# 12VDC_3V3DC_LM2596.net
KiCad netlist of a schematic drawn in Altium Designer
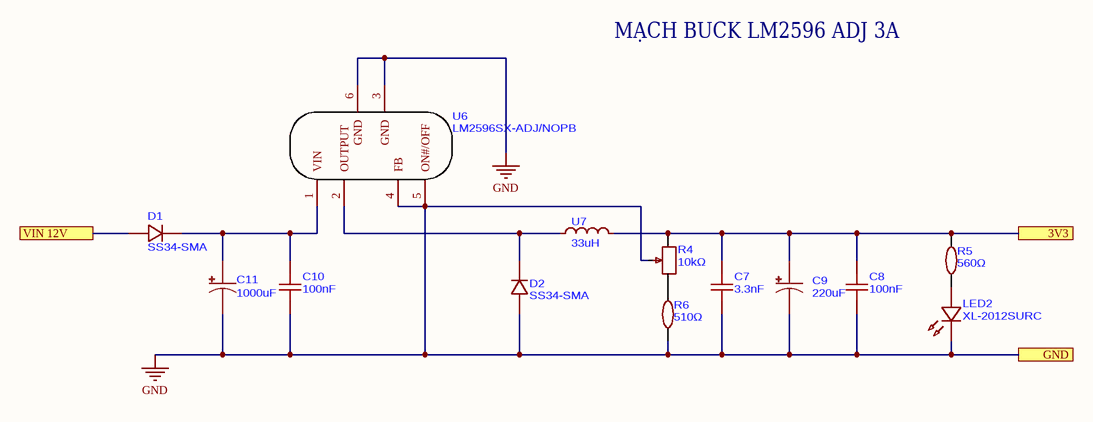
[diagram p0: 12VDC_3V3DC_LM2596.SchDoc]

(export (version "E")
  (design (tool "Eeschema 10.0.6"))
  (components
    (comp (ref "C7")
      (value "3.3nF")
      (footprint "C0805")
      (libsource (lib "CAP 0.1uF") (part "CC0805KRX7R9BB104"))
    )
    (comp (ref "C8")
      (value "100nF")
      (footprint "C0805")
      (libsource (lib "CAP 0.1uF") (part "CC0805KRX7R9BB104"))
    )
    (comp (ref "C9")
      (value "220uF")
      (footprint "CAP-SMD_BD10.0-L10.3-W10.3-LS11.0-R-RD")
      (libsource (lib "CAP +") (part "VEJ102M1ATR-1010"))
    )
    (comp (ref "C10")
      (value "100nF")
      (footprint "C0805")
      (libsource (lib "CAP 0.1uF") (part "CC0805KRX7R9BB104"))
    )
    (comp (ref "C11")
      (value "1000uF")
      (footprint "CAP-SMD_BD10.0-L10.3-W10.3-LS11.0-R-RD")
      (libsource (lib "CAP +") (part "VEJ102M1ATR-1010"))
    )
    (comp (ref "D1")
      (value "SS34-SMA")
      (footprint "SMA_L4.3-W2.6-LS5.2-RD")
      (libsource (lib "Diode SS34") (part "SS34-SMA"))
    )
    (comp (ref "D2")
      (value "SS34-SMA")
      (footprint "SMA_L4.3-W2.6-LS5.2-RD")
      (libsource (lib "Diode SS34") (part "SS34-SMA"))
    )
    (comp (ref "LED2")
      (value "XL-2012SURC")
      (footprint "LED0805-RD_RED")
      (libsource (lib "LED_RED") (part "XL-2012SURC"))
    )
    (comp (ref "R4")
      (value "10kΩ")
      (footprint "RES-ADJ-TH_3296W")
      (libsource (lib "VR 10K") (part "3296W-1-103_C330432"))
    )
    (comp (ref "R5") (value "560Ω") (footprint "R0805") (libsource (lib "RES 1K") (part "RC0805FR-071KL")))
    (comp (ref "R6") (value "510Ω") (footprint "R0805") (libsource (lib "RES 1K") (part "RC0805FR-071KL")))
    (comp (ref "U6")
      (value "LM2596SX-ADJ/NOPB")
      (footprint "TO-263-5_L10.2-W8.9-P1.70-TL")
      (libsource (lib "LM2596") (part "LM2596SX-ADJ/NOPB"))
    )
    (comp (ref "U7")
      (value "33uH")
      (footprint "IND-SMD_L10.0-W10.0_744066100")
      (libsource (lib "Inductor") (part "SRU1038-330Y"))
    )
  )
  (nets
    (net (code "1") (name "/3V3") (class "Default")
      (node (ref "C7") (pin "2") (pinfunction "2_2") (pintype "passive"))
      (node (ref "C8") (pin "2") (pinfunction "2_2") (pintype "passive"))
      (node (ref "C9") (pin "1") (pinfunction "1_1") (pintype "passive"))
      (node (ref "R4") (pin "1") (pinfunction "1_1") (pintype "passive"))
      (node (ref "R5") (pin "2") (pinfunction "2_2") (pintype "passive"))
      (node (ref "U7") (pin "2") (pinfunction "2_2") (pintype "passive"))
    )
    (net (code "2") (name "/VIN 12V") (class "Default")
      (node (ref "D1") (pin "2") (pinfunction "2_2") (pintype "passive"))
    )
    (net (code "3") (name "GND") (class "Default")
      (node (ref "C10") (pin "1") (pinfunction "1_1") (pintype "passive"))
      (node (ref "C11") (pin "2") (pinfunction "2_2") (pintype "passive"))
      (node (ref "C7") (pin "1") (pinfunction "1_1") (pintype "passive"))
      (node (ref "C8") (pin "1") (pinfunction "1_1") (pintype "passive"))
      (node (ref "C9") (pin "2") (pinfunction "2_2") (pintype "passive"))
      (node (ref "D2") (pin "2") (pinfunction "2_2") (pintype "passive"))
      (node (ref "LED2") (pin "1") (pinfunction "K_1") (pintype "passive"))
      (node (ref "R4") (pin "2") (pinfunction "2_2") (pintype "passive"))
      (node (ref "R6") (pin "1") (pinfunction "1_1") (pintype "passive"))
      (node (ref "U6") (pin "3") (pinfunction "GND_3") (pintype "passive"))
      (node (ref "U6") (pin "4") (pinfunction "FB_4") (pintype "passive"))
      (node (ref "U6") (pin "5") (pinfunction "ON#/OFF_5") (pintype "passive"))
      (node (ref "U6") (pin "6") (pinfunction "GND_6") (pintype "passive"))
    )
    (net (code "4") (name "Net-(LED2-A)") (class "Default")
      (node (ref "LED2") (pin "2") (pinfunction "A_2") (pintype "passive"))
      (node (ref "R5") (pin "1") (pinfunction "1_1") (pintype "passive"))
    )
    (net (code "5") (name "Net-(R4-Pad3)") (class "Default")
      (node (ref "R4") (pin "3") (pinfunction "3_3") (pintype "passive"))
      (node (ref "R6") (pin "2") (pinfunction "2_2") (pintype "passive"))
    )
    (net (code "6") (name "Net-(U6-OUTPUT)") (class "Default")
      (node (ref "D2") (pin "1") (pinfunction "1_1") (pintype "passive"))
      (node (ref "U6") (pin "2") (pinfunction "OUTPUT_2") (pintype "passive"))
      (node (ref "U7") (pin "1") (pinfunction "1_1") (pintype "passive"))
    )
    (net (code "7") (name "Net-(U6-VIN)") (class "Default")
      (node (ref "C10") (pin "2") (pinfunction "2_2") (pintype "passive"))
      (node (ref "C11") (pin "1") (pinfunction "1_1") (pintype "passive"))
      (node (ref "D1") (pin "1") (pinfunction "1_1") (pintype "passive"))
      (node (ref "U6") (pin "1") (pinfunction "VIN_1") (pintype "passive"))
    )
  )
)
